# main_board.net
KiCad netlist of a schematic drawn in Altium Designer
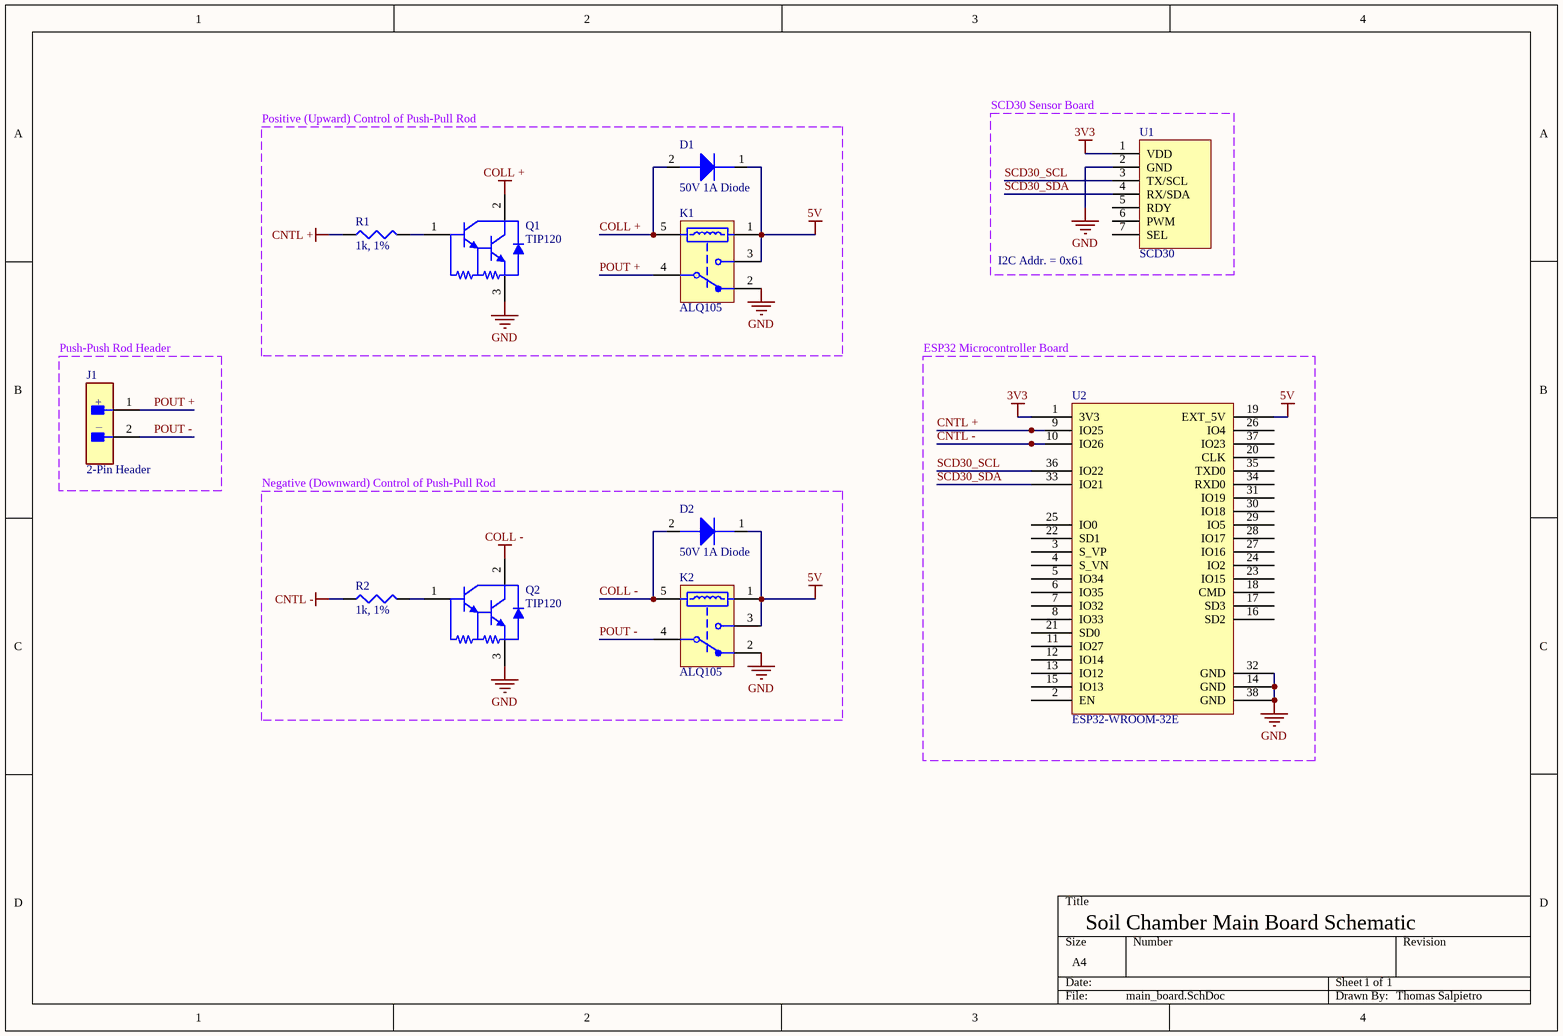
[diagram p0: main_board.SchDoc]

(export (version "E")
  (design (tool "Eeschema 10.0.6"))
  (components
    (comp (ref "D1")
      (value "50V 1A Diode")
      (footprint "S1A")
      (description "Diode Gen Purp 50V 1A Sma")
      (fields
        (field (name "MANUFACTURER") "Sangdest Microelectronics")
        (field (name "MANUFACTURER PART NUMBER") "S1A")
      )
      (libsource (lib "main_board_Schlib1") (part "S1A"))
    )
    (comp (ref "D2")
      (value "50V 1A Diode")
      (footprint "S1A")
      (description "Diode Gen Purp 50V 1A Sma")
      (fields
        (field (name "MANUFACTURER") "Sangdest Microelectronics")
        (field (name "MANUFACTURER PART NUMBER") "S1A")
      )
      (libsource (lib "main_board_Schlib1") (part "S1A"))
    )
    (comp (ref "J1")
      (value "2-Pin Header")
      (footprint "HDR2x1")
      (description "CONN HEADER VERT 2POS 2.54MM")
      (libsource (lib "main_board_Schlib1") (part "3bc925449376181038e59eaffc5286c"))
    )
    (comp (ref "K1")
      (value "ALQ105")
      (footprint "ALQ105")
      (fields (field (name "MANUFACTURER") "Panasonic"))
      (libsource (lib "main_board_Schlib1") (part "PNSC-ALQ105-LQ-5-2000x1000x1600-5"))
    )
    (comp (ref "K2")
      (value "ALQ105")
      (footprint "ALQ105")
      (fields (field (name "MANUFACTURER") "Panasonic"))
      (libsource (lib "main_board_Schlib1") (part "PNSC-ALQ105-LQ-5-2000x1000x1600-5"))
    )
    (comp (ref "Q1")
      (value "TIP120")
      (footprint "TIP120G")
      (description "ON Semi TIP120G NPN Darlington Transistor 8 A 60 V HFE: 1000 3-Pin TO-220")
      (fields
        (field (name "MANUFACTURER") "ON Semiconductor")
        (field (name "MANUFACTURER PART NUMBER") "TIP120G")
      )
      (libsource (lib "main_board_Schlib1") (part "TIP120G"))
    )
    (comp (ref "Q2")
      (value "TIP120")
      (footprint "TIP120G")
      (description "ON Semi TIP120G NPN Darlington Transistor 8 A 60 V HFE: 1000 3-Pin TO-220")
      (fields
        (field (name "MANUFACTURER") "ON Semiconductor")
        (field (name "MANUFACTURER PART NUMBER") "TIP120G")
      )
      (libsource (lib "main_board_Schlib1") (part "TIP120G"))
    )
    (comp (ref "R1")
      (value "1k, 1%")
      (footprint "1206-1k")
      (description "Res 1K Ohm 1% 2W 1206")
      (fields
        (field (name "MANUFACTURER") "TE Connectivity")
        (field (name "MANUFACTURER PART NUMBER") "3503G2B1K0FTDF")
      )
      (libsource (lib "main_board_Schlib1") (part "3503G2B1K0FTDF"))
    )
    (comp (ref "R2")
      (value "1k, 1%")
      (footprint "1206-1k")
      (description "Res 1K Ohm 1% 2W 1206")
      (fields
        (field (name "MANUFACTURER") "TE Connectivity")
        (field (name "MANUFACTURER PART NUMBER") "3503G2B1K0FTDF")
      )
      (libsource (lib "main_board_Schlib1") (part "3503G2B1K0FTDF"))
    )
    (comp (ref "U1")
      (value "SCD30")
      (footprint "SCD30")
      (description "SCD30 Series 5.5 V 75 mA ±3% Carbon Dioxide (CO2) Sensor Module")
      (fields (field (name "MANUFACTURER") "Sensirion"))
      (libsource (lib "main_board_Schlib1") (part "SCD30"))
    )
    (comp (ref "U2")
      (value "ESP32-WROOM-32E")
      (footprint "ESP32")
      (description "ESP32-WROOM-32E 4MB Flash")
      (fields
        (field (name "MANUFACTURER") "Espressif Systems")
        (field (name "MANUFACTURER PART NUMBER") "ESP32-DEVKITC-32E")
      )
      (libsource (lib "main_board_Schlib1") (part "ESP32-DEVKITC-32E"))
    )
  )
  (nets
    (net (code "1") (name "/POUT +") (class "Default")
      (node (ref "J1") (pin "1") (pinfunction "1_1") (pintype "passive"))
      (node (ref "K1") (pin "4") (pinfunction "COM_4") (pintype "passive"))
    )
    (net (code "2") (name "/POUT -") (class "Default")
      (node (ref "J1") (pin "2") (pinfunction "2_2") (pintype "passive"))
      (node (ref "K2") (pin "4") (pinfunction "COM_4") (pintype "passive"))
    )
    (net (code "3") (name "/SCD30_SCL") (class "Default")
      (node (ref "U1") (pin "3") (pinfunction "TX/SCL_3") (pintype "passive"))
      (node (ref "U2") (pin "36") (pinfunction "IO22_36") (pintype "passive"))
    )
    (net (code "4") (name "/SCD30_SDA") (class "Default")
      (node (ref "U1") (pin "4") (pinfunction "RX/SDA_4") (pintype "passive"))
      (node (ref "U2") (pin "33") (pinfunction "IO21_33") (pintype "passive"))
    )
    (net (code "5") (name "3V3") (class "Default")
      (node (ref "U1") (pin "1") (pinfunction "VDD_1") (pintype "power_in"))
      (node (ref "U2") (pin "1") (pinfunction "3V3_1") (pintype "passive"))
    )
    (net (code "6") (name "5V") (class "Default")
      (node (ref "D1") (pin "1") (pinfunction "1_1") (pintype "passive"))
      (node (ref "D2") (pin "1") (pinfunction "1_1") (pintype "passive"))
      (node (ref "K1") (pin "1") (pinfunction "1_1") (pintype "passive"))
      (node (ref "K1") (pin "3") (pinfunction "NO_3") (pintype "passive"))
      (node (ref "K2") (pin "1") (pinfunction "1_1") (pintype "passive"))
      (node (ref "K2") (pin "3") (pinfunction "NO_3") (pintype "passive"))
      (node (ref "U2") (pin "19") (pinfunction "EXT_5V_19") (pintype "passive"))
    )
    (net (code "7") (name "CNTL +") (class "Default")
      (node (ref "R1") (pin "1") (pinfunction "1_1") (pintype "passive"))
      (node (ref "U2") (pin "9") (pinfunction "IO25_9") (pintype "passive"))
    )
    (net (code "8") (name "CNTL -") (class "Default")
      (node (ref "R2") (pin "1") (pinfunction "1_1") (pintype "passive"))
      (node (ref "U2") (pin "10") (pinfunction "IO26_10") (pintype "passive"))
    )
    (net (code "9") (name "COLL +") (class "Default")
      (node (ref "D1") (pin "2") (pinfunction "2_2") (pintype "passive"))
      (node (ref "K1") (pin "5") (pinfunction "5_5") (pintype "passive"))
      (node (ref "Q1") (pin "2") (pinfunction "C_2") (pintype "passive"))
    )
    (net (code "10") (name "COLL -") (class "Default")
      (node (ref "D2") (pin "2") (pinfunction "2_2") (pintype "passive"))
      (node (ref "K2") (pin "5") (pinfunction "5_5") (pintype "passive"))
      (node (ref "Q2") (pin "2") (pinfunction "C_2") (pintype "passive"))
    )
    (net (code "11") (name "GND") (class "Default")
      (node (ref "K1") (pin "2") (pinfunction "NC_2") (pintype "passive"))
      (node (ref "K2") (pin "2") (pinfunction "NC_2") (pintype "passive"))
      (node (ref "Q1") (pin "3") (pinfunction "E_3") (pintype "passive"))
      (node (ref "Q2") (pin "3") (pinfunction "E_3") (pintype "passive"))
      (node (ref "U1") (pin "2") (pinfunction "GND_2") (pintype "power_in"))
      (node (ref "U2") (pin "14") (pinfunction "GND_14") (pintype "passive"))
      (node (ref "U2") (pin "32") (pinfunction "GND_32") (pintype "passive"))
      (node (ref "U2") (pin "38") (pinfunction "GND_38") (pintype "passive"))
    )
    (net (code "12") (name "Net-(Q1-B)") (class "Default")
      (node (ref "Q1") (pin "1") (pinfunction "B_1") (pintype "passive"))
      (node (ref "R1") (pin "2") (pinfunction "2_2") (pintype "passive"))
    )
    (net (code "13") (name "Net-(Q2-B)") (class "Default")
      (node (ref "Q2") (pin "1") (pinfunction "B_1") (pintype "passive"))
      (node (ref "R2") (pin "2") (pinfunction "2_2") (pintype "passive"))
    )
    (net (code "14") (name "unconnected-(U1-PWM-Pad6)") (class "Default")
      (node (ref "U1") (pin "6") (pinfunction "PWM_6") (pintype "passive"))
    )
    (net (code "15") (name "unconnected-(U1-RDY-Pad5)") (class "Default")
      (node (ref "U1") (pin "5") (pinfunction "RDY_5") (pintype "passive"))
    )
    (net (code "16") (name "unconnected-(U1-SEL-Pad7)") (class "Default")
      (node (ref "U1") (pin "7") (pinfunction "SEL_7") (pintype "passive"))
    )
    (net (code "17") (name "unconnected-(U2-CLK-Pad20)") (class "Default")
      (node (ref "U2") (pin "20") (pinfunction "CLK_20") (pintype "passive"))
    )
    (net (code "18") (name "unconnected-(U2-CMD-Pad18)") (class "Default")
      (node (ref "U2") (pin "18") (pinfunction "CMD_18") (pintype "passive"))
    )
    (net (code "19") (name "unconnected-(U2-EN-Pad2)") (class "Default")
      (node (ref "U2") (pin "2") (pinfunction "EN_2") (pintype "passive"))
    )
    (net (code "20") (name "unconnected-(U2-IO0-Pad25)") (class "Default")
      (node (ref "U2") (pin "25") (pinfunction "IO0_25") (pintype "passive"))
    )
    (net (code "21") (name "unconnected-(U2-IO2-Pad24)") (class "Default")
      (node (ref "U2") (pin "24") (pinfunction "IO2_24") (pintype "passive"))
    )
    (net (code "22") (name "unconnected-(U2-IO4-Pad26)") (class "Default")
      (node (ref "U2") (pin "26") (pinfunction "IO4_26") (pintype "passive"))
    )
    (net (code "23") (name "unconnected-(U2-IO5-Pad29)") (class "Default")
      (node (ref "U2") (pin "29") (pinfunction "IO5_29") (pintype "passive"))
    )
    (net (code "24") (name "unconnected-(U2-IO12-Pad13)") (class "Default")
      (node (ref "U2") (pin "13") (pinfunction "IO12_13") (pintype "passive"))
    )
    (net (code "25") (name "unconnected-(U2-IO13-Pad15)") (class "Default")
      (node (ref "U2") (pin "15") (pinfunction "IO13_15") (pintype "passive"))
    )
    (net (code "26") (name "unconnected-(U2-IO14-Pad12)") (class "Default")
      (node (ref "U2") (pin "12") (pinfunction "IO14_12") (pintype "passive"))
    )
    (net (code "27") (name "unconnected-(U2-IO15-Pad23)") (class "Default")
      (node (ref "U2") (pin "23") (pinfunction "IO15_23") (pintype "passive"))
    )
    (net (code "28") (name "unconnected-(U2-IO16-Pad27)") (class "Default")
      (node (ref "U2") (pin "27") (pinfunction "IO16_27") (pintype "passive"))
    )
    (net (code "29") (name "unconnected-(U2-IO17-Pad28)") (class "Default")
      (node (ref "U2") (pin "28") (pinfunction "IO17_28") (pintype "passive"))
    )
    (net (code "30") (name "unconnected-(U2-IO18-Pad30)") (class "Default")
      (node (ref "U2") (pin "30") (pinfunction "IO18_30") (pintype "passive"))
    )
    (net (code "31") (name "unconnected-(U2-IO19-Pad31)") (class "Default")
      (node (ref "U2") (pin "31") (pinfunction "IO19_31") (pintype "passive"))
    )
    (net (code "32") (name "unconnected-(U2-IO23-Pad37)") (class "Default")
      (node (ref "U2") (pin "37") (pinfunction "IO23_37") (pintype "passive"))
    )
    (net (code "33") (name "unconnected-(U2-IO27-Pad11)") (class "Default")
      (node (ref "U2") (pin "11") (pinfunction "IO27_11") (pintype "passive"))
    )
    (net (code "34") (name "unconnected-(U2-IO32-Pad7)") (class "Default")
      (node (ref "U2") (pin "7") (pinfunction "IO32_7") (pintype "passive"))
    )
    (net (code "35") (name "unconnected-(U2-IO33-Pad8)") (class "Default")
      (node (ref "U2") (pin "8") (pinfunction "IO33_8") (pintype "passive"))
    )
    (net (code "36") (name "unconnected-(U2-IO34-Pad5)") (class "Default")
      (node (ref "U2") (pin "5") (pinfunction "IO34_5") (pintype "passive"))
    )
    (net (code "37") (name "unconnected-(U2-IO35-Pad6)") (class "Default")
      (node (ref "U2") (pin "6") (pinfunction "IO35_6") (pintype "passive"))
    )
    (net (code "38") (name "unconnected-(U2-RXD0-Pad34)") (class "Default")
      (node (ref "U2") (pin "34") (pinfunction "RXD0_34") (pintype "passive"))
    )
    (net (code "39") (name "unconnected-(U2-SD0-Pad21)") (class "Default")
      (node (ref "U2") (pin "21") (pinfunction "SD0_21") (pintype "passive"))
    )
    (net (code "40") (name "unconnected-(U2-SD1-Pad22)") (class "Default")
      (node (ref "U2") (pin "22") (pinfunction "SD1_22") (pintype "passive"))
    )
    (net (code "41") (name "unconnected-(U2-SD2-Pad16)") (class "Default")
      (node (ref "U2") (pin "16") (pinfunction "SD2_16") (pintype "passive"))
    )
    (net (code "42") (name "unconnected-(U2-SD3-Pad17)") (class "Default")
      (node (ref "U2") (pin "17") (pinfunction "SD3_17") (pintype "passive"))
    )
    (net (code "43") (name "unconnected-(U2-S_VN-Pad4)") (class "Default")
      (node (ref "U2") (pin "4") (pinfunction "S_VN_4") (pintype "passive"))
    )
    (net (code "44") (name "unconnected-(U2-S_VP-Pad3)") (class "Default")
      (node (ref "U2") (pin "3") (pinfunction "S_VP_3") (pintype "passive"))
    )
    (net (code "45") (name "unconnected-(U2-TXD0-Pad35)") (class "Default")
      (node (ref "U2") (pin "35") (pinfunction "TXD0_35") (pintype "passive"))
    )
  )
)
